# ESP-WROOM-32-Breakout.net
KiCad netlist of a schematic drawn in EAGLE
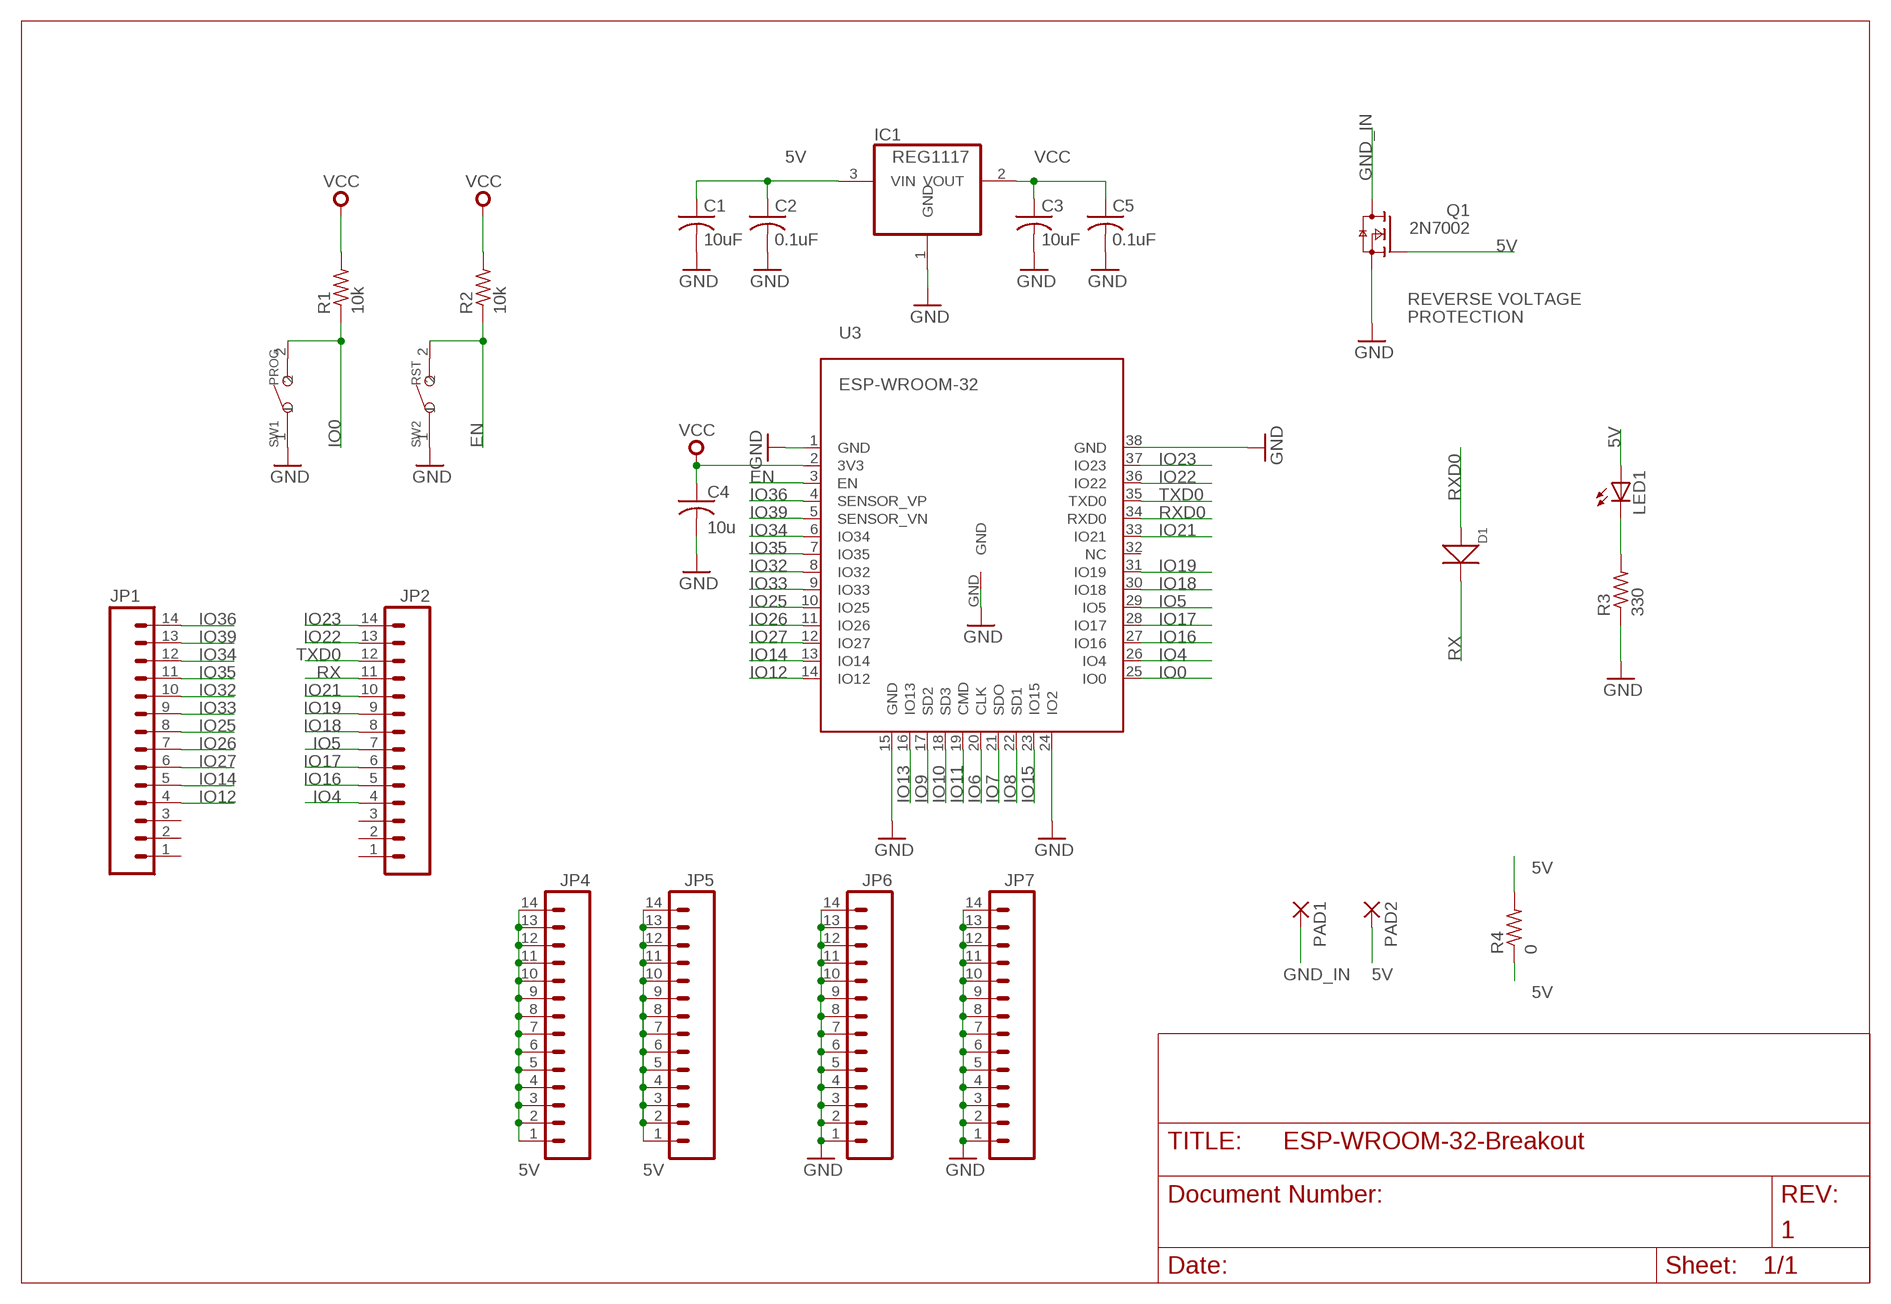
[diagram p0: schematic, sheet 1]

(export (version "E")
  (design (tool "Eeschema 10.0.6"))
  (components
    (comp (ref "C1")
      (value "10uF")
      (footprint "eagle-import:C1206")
      (libsource (lib "eagle-import") (part "C-USC1206"))
    )
    (comp (ref "C2")
      (value "0.1uF")
      (footprint "eagle-import:C1206")
      (libsource (lib "eagle-import") (part "C-USC1206"))
    )
    (comp (ref "C3")
      (value "10uF")
      (footprint "eagle-import:C1206")
      (libsource (lib "eagle-import") (part "C-USC1206"))
    )
    (comp (ref "C4")
      (value "10u")
      (footprint "eagle-import:C1206")
      (libsource (lib "eagle-import") (part "C-USC1206"))
    )
    (comp (ref "C5")
      (value "0.1uF")
      (footprint "eagle-import:C1206")
      (libsource (lib "eagle-import") (part "C-USC1206"))
    )
    (comp (ref "D1")
      (value "DIODE'0805'")
      (footprint "eagle-import:SOD-323")
      (libsource (lib "eagle-import") (part "DIODE'0805'"))
    )
    (comp (ref "IC1")
      (value "REG1117")
      (footprint "eagle-import:SOT223")
      (libsource (lib "eagle-import") (part "REG1117"))
    )
    (comp (ref "JP1")
      (value "M14")
      (footprint "eagle-import:1X14")
      (libsource (lib "eagle-import") (part "M14"))
    )
    (comp (ref "JP2")
      (value "M14")
      (footprint "eagle-import:1X14")
      (libsource (lib "eagle-import") (part "M14"))
    )
    (comp (ref "JP4")
      (value "M14")
      (footprint "eagle-import:1X14")
      (libsource (lib "eagle-import") (part "M14"))
    )
    (comp (ref "JP5")
      (value "M14")
      (footprint "eagle-import:1X14")
      (libsource (lib "eagle-import") (part "M14"))
    )
    (comp (ref "JP6")
      (value "M14")
      (footprint "eagle-import:1X14")
      (libsource (lib "eagle-import") (part "M14"))
    )
    (comp (ref "JP7")
      (value "M14")
      (footprint "eagle-import:1X14")
      (libsource (lib "eagle-import") (part "M14"))
    )
    (comp (ref "LED1")
      (value "LEDCHIPLED_1206")
      (footprint "eagle-import:CHIPLED_1206")
      (libsource (lib "eagle-import") (part "LEDCHIPLED_1206"))
    )
    (comp (ref "PAD1")
      (value "SMD5")
      (footprint "eagle-import:SMD2,54-5,08")
      (libsource (lib "eagle-import") (part "SMD5"))
    )
    (comp (ref "PAD2")
      (value "SMD5")
      (footprint "eagle-import:SMD2,54-5,08")
      (libsource (lib "eagle-import") (part "SMD5"))
    )
    (comp (ref "Q1")
      (value "2N7002")
      (footprint "eagle-import:SOT23")
      (libsource (lib "eagle-import") (part "2N7002E"))
    )
    (comp (ref "R1")
      (value "10k")
      (footprint "eagle-import:R1206")
      (libsource (lib "eagle-import") (part "R-US_R1206"))
    )
    (comp (ref "R2")
      (value "10k")
      (footprint "eagle-import:R1206")
      (libsource (lib "eagle-import") (part "R-US_R1206"))
    )
    (comp (ref "R3")
      (value "330")
      (footprint "eagle-import:R1206")
      (libsource (lib "eagle-import") (part "R-US_R1206"))
    )
    (comp (ref "R4")
      (value "0")
      (footprint "eagle-import:R1206")
      (libsource (lib "eagle-import") (part "R-US_R1206"))
    )
    (comp (ref "SW1")
      (value "PROG")
      (footprint "eagle-import:SW2-4.0-6.0X3.0X2.5MM")
      (libsource (lib "eagle-import") (part "SMD-BUTTON(2P-6.0X3.0X2.5MM)-DHT-1163S"))
    )
    (comp (ref "SW2")
      (value "RST")
      (footprint "eagle-import:SW2-4.0-6.0X3.0X2.5MM")
      (libsource (lib "eagle-import") (part "SMD-BUTTON(2P-6.0X3.0X2.5MM)-DHT-1163S"))
    )
    (comp (ref "U3")
      (value "ESP-WROOM-32")
      (footprint "eagle-import:ESP-WROOM-32")
      (libsource (lib "eagle-import") (part "ESP-WROOM-32"))
    )
  )
  (nets
    (net (code "1") (name "/5V") (class "Default")
      (node (ref "C1") (pin "1") (pinfunction "1_1") (pintype "passive"))
      (node (ref "C2") (pin "1") (pinfunction "1_1") (pintype "passive"))
      (node (ref "IC1") (pin "3") (pinfunction "VIN_3") (pintype "input"))
      (node (ref "JP4") (pin "1") (pinfunction "1_1") (pintype "passive"))
      (node (ref "JP4") (pin "10") (pinfunction "10_10") (pintype "passive"))
      (node (ref "JP4") (pin "11") (pinfunction "11_11") (pintype "passive"))
      (node (ref "JP4") (pin "12") (pinfunction "12_12") (pintype "passive"))
      (node (ref "JP4") (pin "13") (pinfunction "13_13") (pintype "passive"))
      (node (ref "JP4") (pin "14") (pinfunction "14_14") (pintype "passive"))
      (node (ref "JP4") (pin "2") (pinfunction "2_2") (pintype "passive"))
      (node (ref "JP4") (pin "3") (pinfunction "3_3") (pintype "passive"))
      (node (ref "JP4") (pin "4") (pinfunction "4_4") (pintype "passive"))
      (node (ref "JP4") (pin "5") (pinfunction "5_5") (pintype "passive"))
      (node (ref "JP4") (pin "6") (pinfunction "6_6") (pintype "passive"))
      (node (ref "JP4") (pin "7") (pinfunction "7_7") (pintype "passive"))
      (node (ref "JP4") (pin "8") (pinfunction "8_8") (pintype "passive"))
      (node (ref "JP4") (pin "9") (pinfunction "9_9") (pintype "passive"))
      (node (ref "JP5") (pin "1") (pinfunction "1_1") (pintype "passive"))
      (node (ref "JP5") (pin "10") (pinfunction "10_10") (pintype "passive"))
      (node (ref "JP5") (pin "11") (pinfunction "11_11") (pintype "passive"))
      (node (ref "JP5") (pin "12") (pinfunction "12_12") (pintype "passive"))
      (node (ref "JP5") (pin "13") (pinfunction "13_13") (pintype "passive"))
      (node (ref "JP5") (pin "14") (pinfunction "14_14") (pintype "passive"))
      (node (ref "JP5") (pin "2") (pinfunction "2_2") (pintype "passive"))
      (node (ref "JP5") (pin "3") (pinfunction "3_3") (pintype "passive"))
      (node (ref "JP5") (pin "4") (pinfunction "4_4") (pintype "passive"))
      (node (ref "JP5") (pin "5") (pinfunction "5_5") (pintype "passive"))
      (node (ref "JP5") (pin "6") (pinfunction "6_6") (pintype "passive"))
      (node (ref "JP5") (pin "7") (pinfunction "7_7") (pintype "passive"))
      (node (ref "JP5") (pin "8") (pinfunction "8_8") (pintype "passive"))
      (node (ref "JP5") (pin "9") (pinfunction "9_9") (pintype "passive"))
      (node (ref "LED1") (pin "A") (pinfunction "A_A") (pintype "passive"))
      (node (ref "PAD2") (pin "1") (pinfunction "P_1") (pintype "passive"))
      (node (ref "Q1") (pin "1") (pinfunction "G_1") (pintype "passive"))
      (node (ref "R4") (pin "1") (pinfunction "1_1") (pintype "passive"))
      (node (ref "R4") (pin "2") (pinfunction "2_2") (pintype "passive"))
    )
    (net (code "2") (name "/EN") (class "Default")
      (node (ref "R2") (pin "1") (pinfunction "1_1") (pintype "passive"))
      (node (ref "SW2") (pin "2") (pinfunction "2_2") (pintype "bidirectional"))
      (node (ref "U3") (pin "3") (pinfunction "EN_3") (pintype "bidirectional"))
    )
    (net (code "3") (name "/GND_IN") (class "Default")
      (node (ref "PAD1") (pin "1") (pinfunction "P_1") (pintype "passive"))
      (node (ref "Q1") (pin "3") (pinfunction "D_3") (pintype "passive"))
    )
    (net (code "4") (name "/IO0") (class "Default")
      (node (ref "R1") (pin "1") (pinfunction "1_1") (pintype "passive"))
      (node (ref "SW1") (pin "2") (pinfunction "2_2") (pintype "bidirectional"))
      (node (ref "U3") (pin "25") (pinfunction "IO0_25") (pintype "bidirectional"))
    )
    (net (code "5") (name "/IO4") (class "Default")
      (node (ref "JP2") (pin "4") (pinfunction "4_4") (pintype "passive"))
      (node (ref "U3") (pin "26") (pinfunction "IO4_26") (pintype "bidirectional"))
    )
    (net (code "6") (name "/IO5") (class "Default")
      (node (ref "JP2") (pin "7") (pinfunction "7_7") (pintype "passive"))
      (node (ref "U3") (pin "29") (pinfunction "IO5_29") (pintype "bidirectional"))
    )
    (net (code "7") (name "/IO6") (class "Default")
      (node (ref "U3") (pin "20") (pinfunction "CLK_20") (pintype "bidirectional"))
    )
    (net (code "8") (name "/IO7") (class "Default")
      (node (ref "U3") (pin "21") (pinfunction "SDO_21") (pintype "bidirectional"))
    )
    (net (code "9") (name "/IO8") (class "Default")
      (node (ref "U3") (pin "22") (pinfunction "SD1_22") (pintype "bidirectional"))
    )
    (net (code "10") (name "/IO9") (class "Default")
      (node (ref "U3") (pin "17") (pinfunction "SD2_17") (pintype "bidirectional"))
    )
    (net (code "11") (name "/IO10") (class "Default")
      (node (ref "U3") (pin "18") (pinfunction "SD3_18") (pintype "bidirectional"))
    )
    (net (code "12") (name "/IO11") (class "Default")
      (node (ref "U3") (pin "19") (pinfunction "CMD_19") (pintype "bidirectional"))
    )
    (net (code "13") (name "/IO12") (class "Default")
      (node (ref "JP1") (pin "4") (pinfunction "4_4") (pintype "passive"))
      (node (ref "U3") (pin "14") (pinfunction "IO12_14") (pintype "bidirectional"))
    )
    (net (code "14") (name "/IO13") (class "Default")
      (node (ref "U3") (pin "16") (pinfunction "IO13_16") (pintype "bidirectional"))
    )
    (net (code "15") (name "/IO14") (class "Default")
      (node (ref "JP1") (pin "5") (pinfunction "5_5") (pintype "passive"))
      (node (ref "U3") (pin "13") (pinfunction "IO14_13") (pintype "bidirectional"))
    )
    (net (code "16") (name "/IO15") (class "Default")
      (node (ref "U3") (pin "23") (pinfunction "IO15_23") (pintype "bidirectional"))
    )
    (net (code "17") (name "/IO16") (class "Default")
      (node (ref "JP2") (pin "5") (pinfunction "5_5") (pintype "passive"))
      (node (ref "U3") (pin "27") (pinfunction "IO16_27") (pintype "bidirectional"))
    )
    (net (code "18") (name "/IO17") (class "Default")
      (node (ref "JP2") (pin "6") (pinfunction "6_6") (pintype "passive"))
      (node (ref "U3") (pin "28") (pinfunction "IO17_28") (pintype "bidirectional"))
    )
    (net (code "19") (name "/IO18") (class "Default")
      (node (ref "JP2") (pin "8") (pinfunction "8_8") (pintype "passive"))
      (node (ref "U3") (pin "30") (pinfunction "IO18_30") (pintype "bidirectional"))
    )
    (net (code "20") (name "/IO19") (class "Default")
      (node (ref "JP2") (pin "9") (pinfunction "9_9") (pintype "passive"))
      (node (ref "U3") (pin "31") (pinfunction "IO19_31") (pintype "bidirectional"))
    )
    (net (code "21") (name "/IO21") (class "Default")
      (node (ref "JP2") (pin "10") (pinfunction "10_10") (pintype "passive"))
      (node (ref "U3") (pin "33") (pinfunction "IO21_33") (pintype "bidirectional"))
    )
    (net (code "22") (name "/IO22") (class "Default")
      (node (ref "JP2") (pin "13") (pinfunction "13_13") (pintype "passive"))
      (node (ref "U3") (pin "36") (pinfunction "IO22_36") (pintype "bidirectional"))
    )
    (net (code "23") (name "/IO23") (class "Default")
      (node (ref "JP2") (pin "14") (pinfunction "14_14") (pintype "passive"))
      (node (ref "U3") (pin "37") (pinfunction "IO23_37") (pintype "bidirectional"))
    )
    (net (code "24") (name "/IO25") (class "Default")
      (node (ref "JP1") (pin "8") (pinfunction "8_8") (pintype "passive"))
      (node (ref "U3") (pin "10") (pinfunction "IO25_10") (pintype "bidirectional"))
    )
    (net (code "25") (name "/IO26") (class "Default")
      (node (ref "JP1") (pin "7") (pinfunction "7_7") (pintype "passive"))
      (node (ref "U3") (pin "11") (pinfunction "IO26_11") (pintype "bidirectional"))
    )
    (net (code "26") (name "/IO27") (class "Default")
      (node (ref "JP1") (pin "6") (pinfunction "6_6") (pintype "passive"))
      (node (ref "U3") (pin "12") (pinfunction "IO27_12") (pintype "bidirectional"))
    )
    (net (code "27") (name "/IO32") (class "Default")
      (node (ref "JP1") (pin "10") (pinfunction "10_10") (pintype "passive"))
      (node (ref "U3") (pin "8") (pinfunction "IO32_8") (pintype "bidirectional"))
    )
    (net (code "28") (name "/IO33") (class "Default")
      (node (ref "JP1") (pin "9") (pinfunction "9_9") (pintype "passive"))
      (node (ref "U3") (pin "9") (pinfunction "IO33_9") (pintype "bidirectional"))
    )
    (net (code "29") (name "/IO34") (class "Default")
      (node (ref "JP1") (pin "12") (pinfunction "12_12") (pintype "passive"))
      (node (ref "U3") (pin "6") (pinfunction "IO34_6") (pintype "bidirectional"))
    )
    (net (code "30") (name "/IO35") (class "Default")
      (node (ref "JP1") (pin "11") (pinfunction "11_11") (pintype "passive"))
      (node (ref "U3") (pin "7") (pinfunction "IO35_7") (pintype "bidirectional"))
    )
    (net (code "31") (name "/IO36") (class "Default")
      (node (ref "JP1") (pin "14") (pinfunction "14_14") (pintype "passive"))
      (node (ref "U3") (pin "4") (pinfunction "SENSOR_VP_4") (pintype "bidirectional"))
    )
    (net (code "32") (name "/IO39") (class "Default")
      (node (ref "JP1") (pin "13") (pinfunction "13_13") (pintype "passive"))
      (node (ref "U3") (pin "5") (pinfunction "SENSOR_VN_5") (pintype "bidirectional"))
    )
    (net (code "33") (name "/RX") (class "Default")
      (node (ref "D1") (pin "-") (pinfunction "-_-") (pintype "passive"))
      (node (ref "JP2") (pin "11") (pinfunction "11_11") (pintype "passive"))
    )
    (net (code "34") (name "/RXD0") (class "Default")
      (node (ref "D1") (pin "+") (pinfunction "+_+") (pintype "passive"))
      (node (ref "U3") (pin "34") (pinfunction "RXD0_34") (pintype "bidirectional"))
    )
    (net (code "35") (name "/TXD0") (class "Default")
      (node (ref "JP2") (pin "12") (pinfunction "12_12") (pintype "passive"))
      (node (ref "U3") (pin "35") (pinfunction "TXD0_35") (pintype "bidirectional"))
    )
    (net (code "36") (name "GND") (class "Default")
      (node (ref "C1") (pin "2") (pinfunction "2_2") (pintype "passive"))
      (node (ref "C2") (pin "2") (pinfunction "2_2") (pintype "passive"))
      (node (ref "C3") (pin "2") (pinfunction "2_2") (pintype "passive"))
      (node (ref "C4") (pin "2") (pinfunction "2_2") (pintype "passive"))
      (node (ref "C5") (pin "2") (pinfunction "2_2") (pintype "passive"))
      (node (ref "IC1") (pin "1") (pinfunction "GND_1") (pintype "power_in"))
      (node (ref "JP6") (pin "1") (pinfunction "1_1") (pintype "passive"))
      (node (ref "JP6") (pin "10") (pinfunction "10_10") (pintype "passive"))
      (node (ref "JP6") (pin "11") (pinfunction "11_11") (pintype "passive"))
      (node (ref "JP6") (pin "12") (pinfunction "12_12") (pintype "passive"))
      (node (ref "JP6") (pin "13") (pinfunction "13_13") (pintype "passive"))
      (node (ref "JP6") (pin "14") (pinfunction "14_14") (pintype "passive"))
      (node (ref "JP6") (pin "2") (pinfunction "2_2") (pintype "passive"))
      (node (ref "JP6") (pin "3") (pinfunction "3_3") (pintype "passive"))
      (node (ref "JP6") (pin "4") (pinfunction "4_4") (pintype "passive"))
      (node (ref "JP6") (pin "5") (pinfunction "5_5") (pintype "passive"))
      (node (ref "JP6") (pin "6") (pinfunction "6_6") (pintype "passive"))
      (node (ref "JP6") (pin "7") (pinfunction "7_7") (pintype "passive"))
      (node (ref "JP6") (pin "8") (pinfunction "8_8") (pintype "passive"))
      (node (ref "JP6") (pin "9") (pinfunction "9_9") (pintype "passive"))
      (node (ref "JP7") (pin "1") (pinfunction "1_1") (pintype "passive"))
      (node (ref "JP7") (pin "10") (pinfunction "10_10") (pintype "passive"))
      (node (ref "JP7") (pin "11") (pinfunction "11_11") (pintype "passive"))
      (node (ref "JP7") (pin "12") (pinfunction "12_12") (pintype "passive"))
      (node (ref "JP7") (pin "13") (pinfunction "13_13") (pintype "passive"))
      (node (ref "JP7") (pin "14") (pinfunction "14_14") (pintype "passive"))
      (node (ref "JP7") (pin "2") (pinfunction "2_2") (pintype "passive"))
      (node (ref "JP7") (pin "3") (pinfunction "3_3") (pintype "passive"))
      (node (ref "JP7") (pin "4") (pinfunction "4_4") (pintype "passive"))
      (node (ref "JP7") (pin "5") (pinfunction "5_5") (pintype "passive"))
      (node (ref "JP7") (pin "6") (pinfunction "6_6") (pintype "passive"))
      (node (ref "JP7") (pin "7") (pinfunction "7_7") (pintype "passive"))
      (node (ref "JP7") (pin "8") (pinfunction "8_8") (pintype "passive"))
      (node (ref "JP7") (pin "9") (pinfunction "9_9") (pintype "passive"))
      (node (ref "Q1") (pin "2") (pinfunction "S_2") (pintype "passive"))
      (node (ref "R3") (pin "1") (pinfunction "1_1") (pintype "passive"))
      (node (ref "SW1") (pin "1") (pinfunction "1_1") (pintype "bidirectional"))
      (node (ref "SW2") (pin "1") (pinfunction "1_1") (pintype "bidirectional"))
      (node (ref "U3") (pin "1") (pinfunction "GND_1") (pintype "bidirectional"))
      (node (ref "U3") (pin "15") (pinfunction "GND_15") (pintype "bidirectional"))
      (node (ref "U3") (pin "24") (pinfunction "IO2_24") (pintype "bidirectional"))
      (node (ref "U3") (pin "38") (pinfunction "GND_38") (pintype "bidirectional"))
      (node (ref "U3") (pin "GND") (pinfunction "GND_GND") (pintype "bidirectional"))
    )
    (net (code "37") (name "Net-(LED1-PadC)") (class "Default")
      (node (ref "LED1") (pin "C") (pinfunction "C_C") (pintype "passive"))
      (node (ref "R3") (pin "2") (pinfunction "2_2") (pintype "passive"))
    )
    (net (code "38") (name "VCC") (class "Default")
      (node (ref "C3") (pin "1") (pinfunction "1_1") (pintype "passive"))
      (node (ref "C4") (pin "1") (pinfunction "1_1") (pintype "passive"))
      (node (ref "C5") (pin "1") (pinfunction "1_1") (pintype "passive"))
      (node (ref "IC1") (pin "2") (pinfunction "VOUT_2") (pintype "output"))
      (node (ref "R1") (pin "2") (pinfunction "2_2") (pintype "passive"))
      (node (ref "R2") (pin "2") (pinfunction "2_2") (pintype "passive"))
      (node (ref "U3") (pin "2") (pinfunction "3V3_2") (pintype "bidirectional"))
    )
    (net (code "39") (name "unconnected-(JP1-Pad1)") (class "Default")
      (node (ref "JP1") (pin "1") (pinfunction "1_1") (pintype "passive"))
    )
    (net (code "40") (name "unconnected-(JP1-Pad2)") (class "Default")
      (node (ref "JP1") (pin "2") (pinfunction "2_2") (pintype "passive"))
    )
    (net (code "41") (name "unconnected-(JP1-Pad3)") (class "Default")
      (node (ref "JP1") (pin "3") (pinfunction "3_3") (pintype "passive"))
    )
    (net (code "42") (name "unconnected-(JP2-Pad1)") (class "Default")
      (node (ref "JP2") (pin "1") (pinfunction "1_1") (pintype "passive"))
    )
    (net (code "43") (name "unconnected-(JP2-Pad2)") (class "Default")
      (node (ref "JP2") (pin "2") (pinfunction "2_2") (pintype "passive"))
    )
    (net (code "44") (name "unconnected-(JP2-Pad3)") (class "Default")
      (node (ref "JP2") (pin "3") (pinfunction "3_3") (pintype "passive"))
    )
    (net (code "45") (name "unconnected-(U3-NC-Pad32)") (class "Default")
      (node (ref "U3") (pin "32") (pinfunction "NC_32") (pintype "bidirectional"))
    )
  )
)
